# PowerSupply.net
KiCad netlist of a schematic drawn in Altium Designer
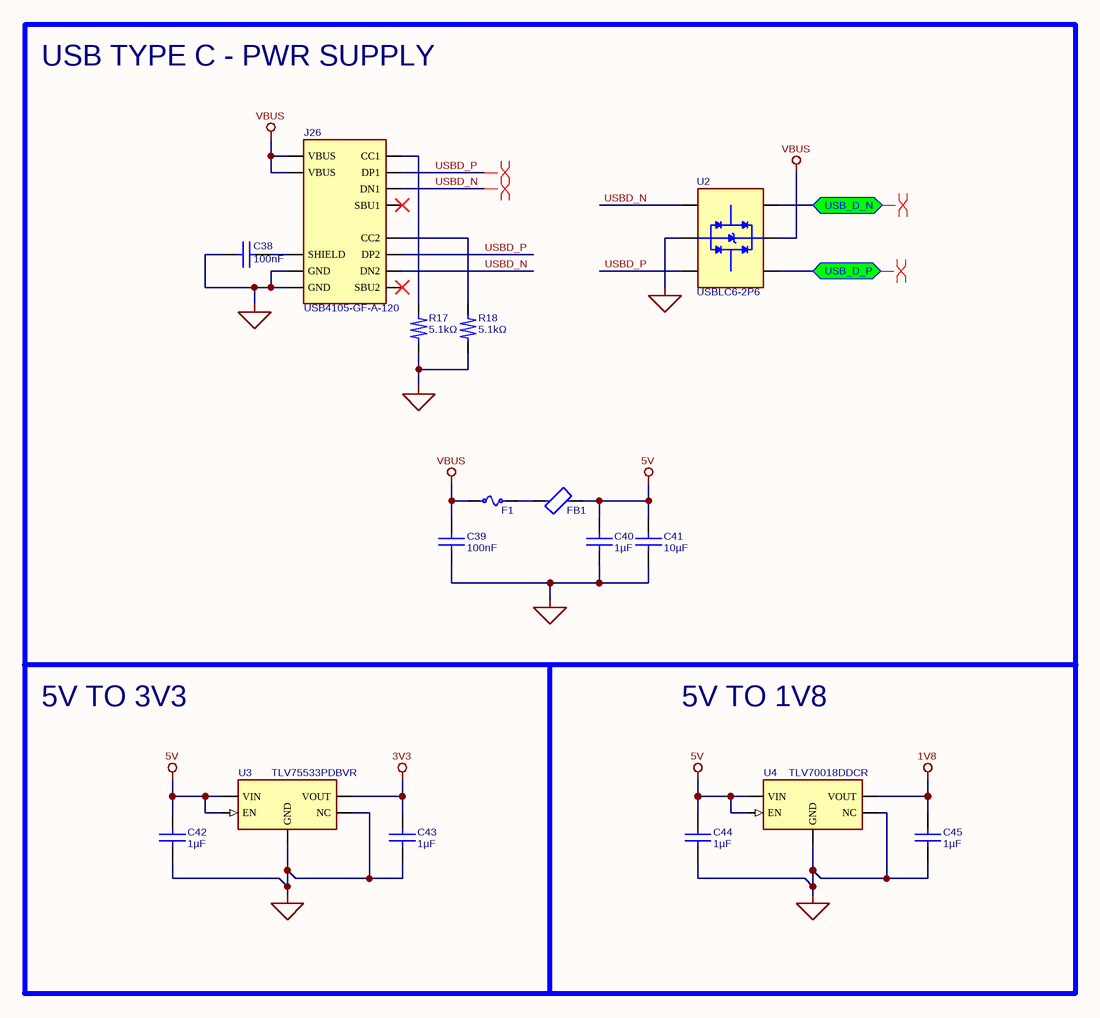
[diagram p0: PowerSupply.SchDoc]

(export (version "E")
  (design (tool "Eeschema 10.0.6"))
  (components
    (comp (ref "C38")
      (value "100nF")
      (footprint "CAPC2012")
      (description "50V 100nF X7R ±10% 0805 Multilayer Ceramic Capacitors MLCC - SMD/SMT ROHS")
      (fields
        (field (name "MANUFACTURER") "YAGEO")
        (field (name "MANUFACTURER PART NUMBER") "CC0805KRX7R9BB104")
      )
      (libsource (lib "Capacitors") (part "CC0805KRX7R9BB104"))
    )
    (comp (ref "C39")
      (value "100nF")
      (footprint "CAPC2012")
      (description "50V 100nF X7R ±10% 0805 Multilayer Ceramic Capacitors MLCC - SMD/SMT ROHS")
      (fields
        (field (name "MANUFACTURER") "YAGEO")
        (field (name "MANUFACTURER PART NUMBER") "CC0805KRX7R9BB104")
      )
      (libsource (lib "Capacitors") (part "CC0805KRX7R9BB104"))
    )
    (comp (ref "C40")
      (value "1µF")
      (footprint "CAPC2012")
      (description "50V 1uF X7R ±10% 0805 Multilayer Ceramic Capacitors MLCC - SMD/SMT ROHS")
      (fields
        (field (name "MANUFACTURER") "Samsung Electro-Mechanics")
        (field (name "MANUFACTURER PART NUMBER") "CL21B105KBFNNNE")
      )
      (libsource (lib "Capacitors") (part "CL21B105KBFNNNE"))
    )
    (comp (ref "C41")
      (value "10µF")
      (footprint "CAPC3216")
      (description "Multilayer Ceramic Capacitors MLCC – SMD/SMT; TDK; C3216X5R1C106K160AA; 10 µF; 1206; 16 V; 16 V")
      (fields
        (field (name "MANUFACTURER") "TDK")
        (field (name "MANUFACTURER PART NUMBER") "C3216X5R1C106K160AA")
      )
      (libsource (lib "Capacitors") (part "C3216X5R1C106K160AA"))
    )
    (comp (ref "C42")
      (value "1µF")
      (footprint "CAPC2012")
      (description "50V 1uF X7R ±10% 0805 Multilayer Ceramic Capacitors MLCC - SMD/SMT ROHS")
      (fields
        (field (name "MANUFACTURER") "Samsung Electro-Mechanics")
        (field (name "MANUFACTURER PART NUMBER") "CL21B105KBFNNNE")
      )
      (libsource (lib "Capacitors") (part "CL21B105KBFNNNE"))
    )
    (comp (ref "C43")
      (value "1µF")
      (footprint "CAPC2012")
      (description "50V 1uF X7R ±10% 0805 Multilayer Ceramic Capacitors MLCC - SMD/SMT ROHS")
      (fields
        (field (name "MANUFACTURER") "Samsung Electro-Mechanics")
        (field (name "MANUFACTURER PART NUMBER") "CL21B105KBFNNNE")
      )
      (libsource (lib "Capacitors") (part "CL21B105KBFNNNE"))
    )
    (comp (ref "C44")
      (value "1µF")
      (footprint "CAPC2012")
      (description "50V 1uF X7R ±10% 0805 Multilayer Ceramic Capacitors MLCC - SMD/SMT ROHS")
      (fields
        (field (name "MANUFACTURER") "Samsung Electro-Mechanics")
        (field (name "MANUFACTURER PART NUMBER") "CL21B105KBFNNNE")
      )
      (libsource (lib "Capacitors") (part "CL21B105KBFNNNE"))
    )
    (comp (ref "C45")
      (value "1µF")
      (footprint "CAPC2012")
      (description "50V 1uF X7R ±10% 0805 Multilayer Ceramic Capacitors MLCC - SMD/SMT ROHS")
      (fields
        (field (name "MANUFACTURER") "Samsung Electro-Mechanics")
        (field (name "MANUFACTURER PART NUMBER") "CL21B105KBFNNNE")
      )
      (libsource (lib "Capacitors") (part "CL21B105KBFNNNE"))
    )
    (comp (ref "F1")
      (value "0467002.NR")
      (footprint "FUSC1608X31N")
      (description "Electric Fuse, Very Fast Blow, 2A, 32VAC, 32VDC, 35A (IR), Surface Mount, 0603")
      (fields (field (name "MANUFACTURER") "Littelfuse Inc"))
      (libsource (lib "Fuses") (part "0467002.NR"))
    )
    (comp (ref "FB1")
      (value "BLM21PG221SN1D")
      (footprint "FP-BLM21-0_2-t0_85-e0_5-MFG")
      (description "220 Ohms @ 100 MHz 1 Power Line Ferrite Bead 0805 (2012 Metric) 2A 45mOhm")
      (fields (field (name "MANUFACTURER") "Murata Electronics"))
      (libsource (lib "FerriteBeads") (part "BLM21PG221SN1D"))
    )
    (comp (ref "J26")
      (value "USB4105-GF-A-120")
      (footprint "GCT_USB4105-GF-A-120")
      (description "USB Connector, 24 Contact(s), Female, Right Angle, Solder Terminal, Locking, Receptacle")
      (fields (field (name "MANUFACTURER") "GCT"))
      (libsource (lib "Connectors") (part "USB4105-GF-A-120"))
    )
    (comp (ref "R17")
      (value "5.1kΩ")
      (footprint "RESC1608")
      (description "Res Thick Film 0603 5.1K Ohm 1% 0.1W(1/10W) ±100ppm/C Pad SMD T/R")
      (fields
        (field (name "MANUFACTURER") "YAGEO")
        (field (name "MANUFACTURER PART NUMBER") "RC0603FR-075K1L")
      )
      (libsource (lib "Resistors") (part "RC0603FR-075K1L"))
    )
    (comp (ref "R18")
      (value "5.1kΩ")
      (footprint "RESC1608")
      (description "Res Thick Film 0603 5.1K Ohm 1% 0.1W(1/10W) ±100ppm/C Pad SMD T/R")
      (fields
        (field (name "MANUFACTURER") "YAGEO")
        (field (name "MANUFACTURER PART NUMBER") "RC0603FR-075K1L")
      )
      (libsource (lib "Resistors") (part "RC0603FR-075K1L"))
    )
    (comp (ref "U2")
      (value "USBLC6-2P6")
      (footprint "SOT50P160X60-6N")
      (description "Tvs Diodes & Esd Suppressors; USBLC6-2P6; Stmicroelectronics; 5 V; 17 V; 6 V; 6 V")
      (fields (field (name "MANUFACTURER") "STMicroelectronics"))
      (libsource (lib "ICs") (part "USBLC6-2P6"))
    )
    (comp (ref "U3")
      (value "TLV75533PDBVR")
      (footprint "SOT95P280X110-5N")
      (description "500mA high-PSRR low-IQ low-dropout voltage regulator with enable 5-SOT-23 -40 to 125")
      (fields (field (name "MANUFACTURER") "Texas Instruments"))
      (libsource (lib "ICs") (part "TLV75533PDBVR"))
    )
    (comp (ref "U4")
      (value "TLV70018DDCR")
      (footprint "SOT95P280X110-5N")
      (description "200-mA, high-PSRR, low-IQ, low-dropout voltage regulator with enable 5-SOT-23-THIN -40 to 125")
      (fields (field (name "MANUFACTURER") "Texas Instruments"))
      (libsource (lib "ICs") (part "TLV70018DDCR"))
    )
  )
  (nets
    (net (code "1") (name "/USBD_N") (class "Default")
      (node (ref "J26") (pin "A7") (pinfunction "DN1_A7") (pintype "bidirectional"))
      (node (ref "J26") (pin "B7") (pinfunction "DN2_B7") (pintype "bidirectional"))
      (node (ref "U2") (pin "1") (pinfunction "I/O1_1_1") (pintype "bidirectional"))
    )
    (net (code "2") (name "/USBD_P") (class "Default")
      (node (ref "J26") (pin "A6") (pinfunction "DP1_A6") (pintype "bidirectional"))
      (node (ref "J26") (pin "B6") (pinfunction "DP2_B6") (pintype "bidirectional"))
      (node (ref "U2") (pin "3") (pinfunction "I/O2_1_3") (pintype "bidirectional"))
    )
    (net (code "3") (name "/USB_D_N") (class "Default")
      (node (ref "U2") (pin "6") (pinfunction "I/O1_2_6") (pintype "bidirectional"))
    )
    (net (code "4") (name "/USB_D_P") (class "Default")
      (node (ref "U2") (pin "4") (pinfunction "I/O2_2_4") (pintype "bidirectional"))
    )
    (net (code "5") (name "1V8") (class "Default")
      (node (ref "C45") (pin "1") (pinfunction "1_1") (pintype "passive"))
      (node (ref "U4") (pin "5") (pinfunction "VOUT_5") (pintype "power_in"))
    )
    (net (code "6") (name "3V3") (class "Default")
      (node (ref "C43") (pin "1") (pinfunction "1_1") (pintype "passive"))
      (node (ref "U3") (pin "5") (pinfunction "VOUT_5") (pintype "power_in"))
    )
    (net (code "7") (name "5V") (class "Default")
      (node (ref "C40") (pin "1") (pinfunction "1_1") (pintype "passive"))
      (node (ref "C41") (pin "1") (pinfunction "1_1") (pintype "passive"))
      (node (ref "C42") (pin "1") (pinfunction "1_1") (pintype "passive"))
      (node (ref "C44") (pin "1") (pinfunction "1_1") (pintype "passive"))
      (node (ref "FB1") (pin "2") (pinfunction "2_2") (pintype "passive"))
      (node (ref "U3") (pin "1") (pinfunction "VIN_1") (pintype "power_in"))
      (node (ref "U3") (pin "3") (pinfunction "EN_3") (pintype "input"))
      (node (ref "U4") (pin "1") (pinfunction "VIN_1") (pintype "power_in"))
      (node (ref "U4") (pin "3") (pinfunction "EN_3") (pintype "input"))
    )
    (net (code "8") (name "GND") (class "Default")
      (node (ref "C38") (pin "1") (pinfunction "1_1") (pintype "passive"))
      (node (ref "C39") (pin "1") (pinfunction "1_1") (pintype "passive"))
      (node (ref "C40") (pin "2") (pinfunction "2_2") (pintype "passive"))
      (node (ref "C41") (pin "2") (pinfunction "2_2") (pintype "passive"))
      (node (ref "C42") (pin "2") (pinfunction "2_2") (pintype "passive"))
      (node (ref "C43") (pin "2") (pinfunction "2_2") (pintype "passive"))
      (node (ref "C44") (pin "2") (pinfunction "2_2") (pintype "passive"))
      (node (ref "C45") (pin "2") (pinfunction "2_2") (pintype "passive"))
      (node (ref "J26") (pin "A1_B12") (pinfunction "GND_A1_B12") (pintype "power_in"))
      (node (ref "J26") (pin "B1_A12") (pinfunction "GND_B1_A12") (pintype "power_in"))
      (node (ref "R17") (pin "1") (pinfunction "1_1") (pintype "passive"))
      (node (ref "R18") (pin "1") (pinfunction "1_1") (pintype "passive"))
      (node (ref "U2") (pin "2") (pinfunction "GND_2") (pintype "power_in"))
      (node (ref "U3") (pin "2") (pinfunction "GND_2") (pintype "power_in"))
      (node (ref "U3") (pin "4") (pinfunction "NC_4") (pintype "passive"))
      (node (ref "U4") (pin "2") (pinfunction "GND_2") (pintype "power_in"))
      (node (ref "U4") (pin "4") (pinfunction "NC_4") (pintype "passive"))
    )
    (net (code "9") (name "Net-(F1-Pad1)") (class "Default")
      (node (ref "F1") (pin "1") (pinfunction "1_1") (pintype "passive"))
      (node (ref "FB1") (pin "1") (pinfunction "1_1") (pintype "passive"))
    )
    (net (code "10") (name "Net-(J26-CC1)") (class "Default")
      (node (ref "J26") (pin "A5") (pinfunction "CC1_A5") (pintype "bidirectional"))
      (node (ref "R17") (pin "2") (pinfunction "2_2") (pintype "passive"))
    )
    (net (code "11") (name "Net-(J26-CC2)") (class "Default")
      (node (ref "J26") (pin "B5") (pinfunction "CC2_B5") (pintype "bidirectional"))
      (node (ref "R18") (pin "2") (pinfunction "2_2") (pintype "passive"))
    )
    (net (code "12") (name "Net-(J26-SHIELD)") (class "Default")
      (node (ref "C38") (pin "2") (pinfunction "2_2") (pintype "passive"))
      (node (ref "J26") (pin "SH") (pinfunction "SHIELD_SH") (pintype "power_in"))
    )
    (net (code "13") (name "VBUS") (class "Default")
      (node (ref "C39") (pin "2") (pinfunction "2_2") (pintype "passive"))
      (node (ref "F1") (pin "2") (pinfunction "2_2") (pintype "passive"))
      (node (ref "J26") (pin "A4_B9") (pinfunction "VBUS_A4_B9") (pintype "power_in"))
      (node (ref "J26") (pin "B4_A9") (pinfunction "VBUS_B4_A9") (pintype "power_in"))
      (node (ref "U2") (pin "5") (pinfunction "VBUS_5") (pintype "power_in"))
    )
    (net (code "14") (name "unconnected-(J26-SBU1-PadA8)") (class "Default")
      (node (ref "J26") (pin "A8") (pinfunction "SBU1_A8") (pintype "bidirectional+no_connect"))
    )
    (net (code "15") (name "unconnected-(J26-SBU2-PadB8)") (class "Default")
      (node (ref "J26") (pin "B8") (pinfunction "SBU2_B8") (pintype "bidirectional+no_connect"))
    )
  )
)
